# Camera_Display.net
KiCad netlist of a schematic drawn in Altium Designer
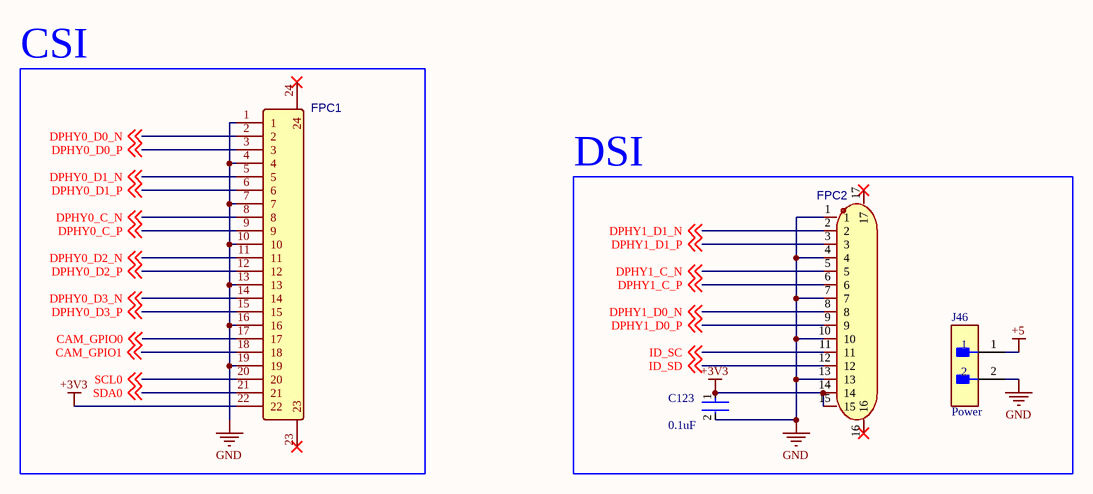
[diagram p0: Camera + Display.SchDoc]

(export (version "E")
  (design (tool "Eeschema 10.0.6"))
  (components
    (comp (ref "C123")
      (value "0.1uF")
      (footprint "FP-C0402-BB-MFG")
      (description "C307331")
      (fields
        (field (name "TOLERANCE") "0.2")
        (field (name "OCTOPART") "https://octopart.com/c0402c104m3pac7867-kemet-84304880")
      )
      (libsource (lib "Altium Content Vault") (part "b4654b650e69147ec39a6b967a45e02"))
    )
    (comp (ref "FPC1")
      (value "AFC01-S22FCA-00")
      (footprint "FPC-SMD_P0.5-22P_FGS-XJ-H2.0")
      (description "C262668")
      (fields (field (name "MANUFACTURER") "JS(钜硕电子)") (field (name "CONTRIBUTOR") "LCSC"))
      (libsource (lib "Schlib1") (part "CSI Bottom Contact Right Angle"))
    )
    (comp (ref "FPC2")
      (value "HC-FPC-1.0-15P-FHH20")
      (footprint "FPC-SMD_15P-P0.50_HC-FPC-1.0-15P-FHH20")
      (description "C49166884")
      (fields (field (name "MANUFACTURER") "HC(虹成电子)"))
      (libsource (lib "Schlib1") (part "DSI Top and Bottom Connector"))
    )
    (comp (ref "J46")
      (value "Power")
      (footprint "FP-TSW-102-14-G-S-MFG")
      (description "CONN HEADER VERT 2POS 2.54MM")
      (libsource (lib "Altium Content Vault") (part "88c1139f9d239099ffebecbe3f7647a"))
    )
  )
  (nets
    (net (code "1") (name "+3V3") (class "Default")
      (node (ref "C123") (pin "1") (pinfunction "1_1") (pintype "passive"))
      (node (ref "FPC1") (pin "22") (pinfunction "22_22") (pintype "passive"))
      (node (ref "FPC2") (pin "14") (pinfunction "14_14") (pintype "passive"))
      (node (ref "FPC2") (pin "15") (pinfunction "15_15") (pintype "passive"))
    )
    (net (code "2") (name "+5") (class "Default")
      (node (ref "J46") (pin "1") (pinfunction "1_1") (pintype "passive"))
    )
    (net (code "3") (name "CAM_GPIO0") (class "Default")
      (node (ref "FPC1") (pin "17") (pinfunction "17_17") (pintype "passive"))
    )
    (net (code "4") (name "CAM_GPIO1") (class "Default")
      (node (ref "FPC1") (pin "18") (pinfunction "18_18") (pintype "passive"))
    )
    (net (code "5") (name "DPHY0_C_N") (class "Default")
      (node (ref "FPC1") (pin "8") (pinfunction "8_8") (pintype "passive"))
    )
    (net (code "6") (name "DPHY0_C_P") (class "Default")
      (node (ref "FPC1") (pin "9") (pinfunction "9_9") (pintype "passive"))
    )
    (net (code "7") (name "DPHY0_D0_N") (class "Default")
      (node (ref "FPC1") (pin "2") (pinfunction "2_2") (pintype "passive"))
    )
    (net (code "8") (name "DPHY0_D0_P") (class "Default")
      (node (ref "FPC1") (pin "3") (pinfunction "3_3") (pintype "passive"))
    )
    (net (code "9") (name "DPHY0_D1_N") (class "Default")
      (node (ref "FPC1") (pin "5") (pinfunction "5_5") (pintype "passive"))
    )
    (net (code "10") (name "DPHY0_D1_P") (class "Default")
      (node (ref "FPC1") (pin "6") (pinfunction "6_6") (pintype "passive"))
    )
    (net (code "11") (name "DPHY0_D2_N") (class "Default")
      (node (ref "FPC1") (pin "11") (pinfunction "11_11") (pintype "passive"))
    )
    (net (code "12") (name "DPHY0_D2_P") (class "Default")
      (node (ref "FPC1") (pin "12") (pinfunction "12_12") (pintype "passive"))
    )
    (net (code "13") (name "DPHY0_D3_N") (class "Default")
      (node (ref "FPC1") (pin "14") (pinfunction "14_14") (pintype "passive"))
    )
    (net (code "14") (name "DPHY0_D3_P") (class "Default")
      (node (ref "FPC1") (pin "15") (pinfunction "15_15") (pintype "passive"))
    )
    (net (code "15") (name "DPHY1_C_N") (class "Default")
      (node (ref "FPC2") (pin "5") (pinfunction "5_5") (pintype "passive"))
    )
    (net (code "16") (name "DPHY1_C_P") (class "Default")
      (node (ref "FPC2") (pin "6") (pinfunction "6_6") (pintype "passive"))
    )
    (net (code "17") (name "DPHY1_D0_N") (class "Default")
      (node (ref "FPC2") (pin "8") (pinfunction "8_8") (pintype "passive"))
    )
    (net (code "18") (name "DPHY1_D0_P") (class "Default")
      (node (ref "FPC2") (pin "9") (pinfunction "9_9") (pintype "passive"))
    )
    (net (code "19") (name "DPHY1_D1_N") (class "Default")
      (node (ref "FPC2") (pin "2") (pinfunction "2_2") (pintype "passive"))
    )
    (net (code "20") (name "DPHY1_D1_P") (class "Default")
      (node (ref "FPC2") (pin "3") (pinfunction "3_3") (pintype "passive"))
    )
    (net (code "21") (name "GND") (class "Default")
      (node (ref "C123") (pin "2") (pinfunction "2_2") (pintype "passive"))
      (node (ref "FPC1") (pin "1") (pinfunction "1_1") (pintype "passive"))
      (node (ref "FPC1") (pin "10") (pinfunction "10_10") (pintype "passive"))
      (node (ref "FPC1") (pin "13") (pinfunction "13_13") (pintype "passive"))
      (node (ref "FPC1") (pin "16") (pinfunction "16_16") (pintype "passive"))
      (node (ref "FPC1") (pin "19") (pinfunction "19_19") (pintype "passive"))
      (node (ref "FPC1") (pin "4") (pinfunction "4_4") (pintype "passive"))
      (node (ref "FPC1") (pin "7") (pinfunction "7_7") (pintype "passive"))
      (node (ref "FPC2") (pin "1") (pinfunction "1_1") (pintype "passive"))
      (node (ref "FPC2") (pin "10") (pinfunction "10_10") (pintype "passive"))
      (node (ref "FPC2") (pin "13") (pinfunction "13_13") (pintype "passive"))
      (node (ref "FPC2") (pin "4") (pinfunction "4_4") (pintype "passive"))
      (node (ref "FPC2") (pin "7") (pinfunction "7_7") (pintype "passive"))
      (node (ref "J46") (pin "2") (pinfunction "2_2") (pintype "passive"))
    )
    (net (code "22") (name "ID_SC") (class "Default")
      (node (ref "FPC2") (pin "11") (pinfunction "11_11") (pintype "passive"))
    )
    (net (code "23") (name "ID_SD") (class "Default")
      (node (ref "FPC2") (pin "12") (pinfunction "12_12") (pintype "passive"))
    )
    (net (code "24") (name "SCL0") (class "Default")
      (node (ref "FPC1") (pin "20") (pinfunction "20_20") (pintype "passive"))
    )
    (net (code "25") (name "SDA0") (class "Default")
      (node (ref "FPC1") (pin "21") (pinfunction "21_21") (pintype "passive"))
    )
    (net (code "26") (name "unconnected-(FPC1-Pad23)") (class "Default")
      (node (ref "FPC1") (pin "23") (pinfunction "23_23") (pintype "passive+no_connect"))
    )
    (net (code "27") (name "unconnected-(FPC1-Pad24)") (class "Default")
      (node (ref "FPC1") (pin "24") (pinfunction "24_24") (pintype "passive+no_connect"))
    )
    (net (code "28") (name "unconnected-(FPC2-Pad16)") (class "Default")
      (node (ref "FPC2") (pin "16") (pinfunction "16_16") (pintype "passive+no_connect"))
    )
    (net (code "29") (name "unconnected-(FPC2-Pad17)") (class "Default")
      (node (ref "FPC2") (pin "17") (pinfunction "17_17") (pintype "passive+no_connect"))
    )
  )
)
